# CFG_FLASH_Update.net
KiCad netlist of a schematic drawn in Altium Designer
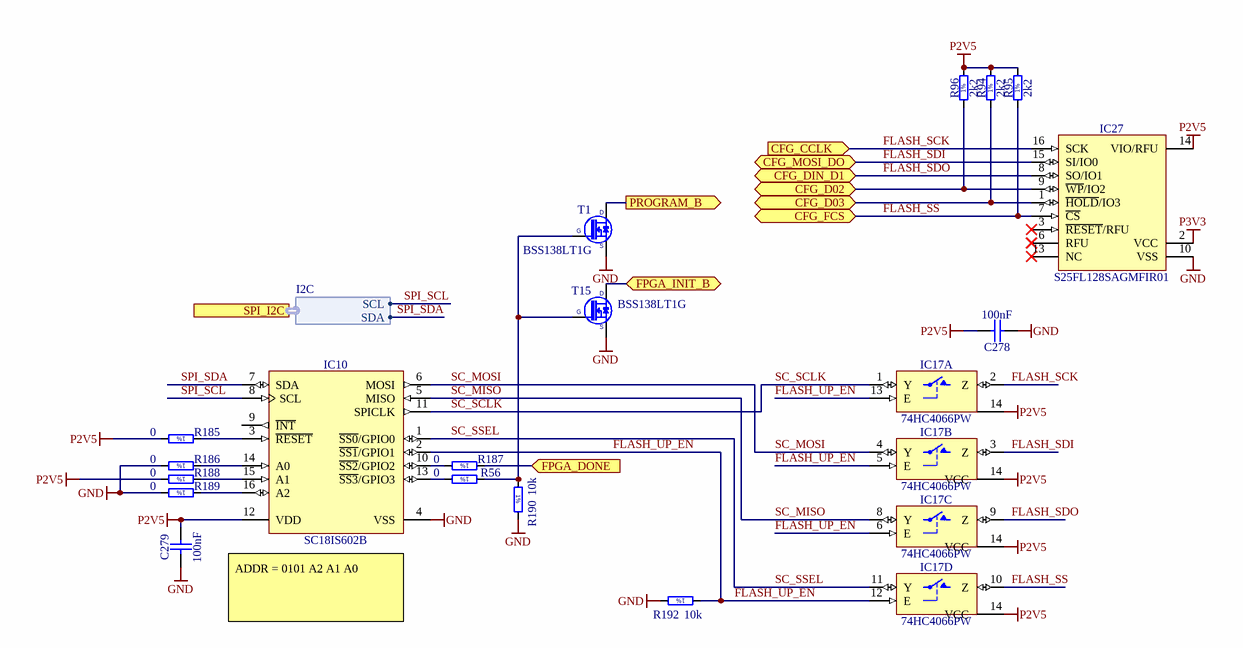
[diagram p0: CFG_FLASH_Update.SchDoc]

(export (version "E")
  (design (tool "Eeschema 10.0.6"))
  (components
    (comp (ref "C278")
      (value "100nF")
      (footprint "CAPC1005X55N")
      (description "Non-polarised capacitor")
      (fields
        (field (name "PART NUMBER") "CC0402_100NF_16V_10%_X5R")
        (field (name "VOLTAGE") "16V")
        (field (name "AUTHOR") "CERN DEM JLC")
      )
      (libsource (lib "Capacitors") (part "Capacitor - non polarized"))
    )
    (comp (ref "C279")
      (value "100nF")
      (footprint "CAPC1005X55N")
      (description "Non-polarised capacitor")
      (fields
        (field (name "PART NUMBER") "CC0402_100NF_16V_10%_X5R")
        (field (name "VOLTAGE") "16V")
        (field (name "AUTHOR") "CERN DEM JLC")
      )
      (libsource (lib "Capacitors") (part "Capacitor - non polarized"))
    )
    (comp (ref "IC10")
      (value "SC18IS602B")
      (footprint "SOP65P640X110-16N")
      (description "I2C-bus to SPI bridge")
      (fields (field (name "MANUFACTURER") "NXP SEMICONDUCTORS") (field (name "AUTHOR") "CERN DEM MR"))
      (libsource (lib "ICs And Semiconductors") (part "SC18IS602B"))
    )
    (comp (ref "IC17")
      (value "74HC4066PW")
      (footprint "SOP65P640X110-14N")
      (fields (field (name "MANUFACTURER") "NXP SEMICONDUCTORS") (field (name "AUTHOR") "CERN DEM JLC"))
      (libsource (lib "ICs And Semiconductors") (part "4066"))
    )
    (comp (ref "IC27")
      (value "S25FL128SAGMFIR01")
      (footprint "SOIC127P1030X265-16N")
      (fields (field (name "MANUFACTURER") "SPANSION") (field (name "AUTHOR") "CERN DEM JLC"))
      (libsource (lib "ICs And Semiconductors") (part "S25FL128SAGMFIR01"))
    )
    (comp (ref "R56")
      (value "0")
      (footprint "RESC1608X55N")
      (description "Resistor - 1%")
      (fields
        (field (name "PART NUMBER") "R0603_0R_JUMPER")
        (field (name "MANUFACTURER") "GENERIC")
        (field (name "AUTHOR") "CERN DEM JLC")
      )
      (libsource (lib "Resistors") (part "Resistor - 1%"))
    )
    (comp (ref "R94")
      (value "2k2")
      (footprint "RESC1005X40N")
      (description "Resistor - 1%")
      (fields
        (field (name "PART NUMBER") "R0402_2K2_1%_0.0625W_100PPM")
        (field (name "POWER") "0.0625W")
        (field (name "AUTHOR") "CERN DEM JLC")
      )
      (libsource (lib "Resistors") (part "Resistor - 1%"))
    )
    (comp (ref "R95")
      (value "2k2")
      (footprint "RESC1005X40N")
      (description "Resistor - 1%")
      (fields
        (field (name "PART NUMBER") "R0402_2K2_1%_0.0625W_100PPM")
        (field (name "POWER") "0.0625W")
        (field (name "AUTHOR") "CERN DEM JLC")
      )
      (libsource (lib "Resistors") (part "Resistor - 1%"))
    )
    (comp (ref "R96")
      (value "2k2")
      (footprint "RESC1005X40N")
      (description "Resistor - 1%")
      (fields
        (field (name "PART NUMBER") "R0402_2K2_1%_0.0625W_100PPM")
        (field (name "POWER") "0.0625W")
        (field (name "AUTHOR") "CERN DEM JLC")
      )
      (libsource (lib "Resistors") (part "Resistor - 1%"))
    )
    (comp (ref "R185")
      (value "0")
      (footprint "RESC1608X55N")
      (description "Resistor - 1%")
      (fields
        (field (name "PART NUMBER") "R0603_0R_JUMPER")
        (field (name "MANUFACTURER") "GENERIC")
        (field (name "AUTHOR") "CERN DEM JLC")
      )
      (libsource (lib "Resistors") (part "Resistor - 1%"))
    )
    (comp (ref "R186")
      (value "0")
      (footprint "RESC1608X55N")
      (description "Resistor - 1%")
      (fields
        (field (name "PART NUMBER") "R0603_0R_JUMPER")
        (field (name "MANUFACTURER") "GENERIC")
        (field (name "AUTHOR") "CERN DEM JLC")
      )
      (libsource (lib "Resistors") (part "Resistor - 1%"))
    )
    (comp (ref "R187")
      (value "0")
      (footprint "RESC1608X55N")
      (description "Resistor - 1%")
      (fields
        (field (name "PART NUMBER") "R0603_0R_JUMPER")
        (field (name "MANUFACTURER") "GENERIC")
        (field (name "AUTHOR") "CERN DEM JLC")
      )
      (libsource (lib "Resistors") (part "Resistor - 1%"))
    )
    (comp (ref "R188")
      (value "0")
      (footprint "RESC1608X55N")
      (description "Resistor - 1%")
      (fields
        (field (name "PART NUMBER") "R0603_0R_JUMPER")
        (field (name "MANUFACTURER") "GENERIC")
        (field (name "AUTHOR") "CERN DEM JLC")
      )
      (libsource (lib "Resistors") (part "Resistor - 1%"))
    )
    (comp (ref "R189")
      (value "0")
      (footprint "RESC1608X55N")
      (description "Resistor - 1%")
      (fields
        (field (name "PART NUMBER") "R0603_0R_JUMPER")
        (field (name "MANUFACTURER") "GENERIC")
        (field (name "AUTHOR") "CERN DEM JLC")
      )
      (libsource (lib "Resistors") (part "Resistor - 1%"))
    )
    (comp (ref "R190")
      (value "10k")
      (footprint "RESC1005X40N")
      (description "Resistor - 1%")
      (fields
        (field (name "PART NUMBER") "R0402_10K_1%_0.0625W_100PPM")
        (field (name "POWER") "0.0625W")
        (field (name "AUTHOR") "CERN DEM JLC")
      )
      (libsource (lib "Resistors") (part "Resistor - 1%"))
    )
    (comp (ref "R192")
      (value "10k")
      (footprint "RESC1005X40N")
      (description "Resistor - 1%")
      (fields
        (field (name "PART NUMBER") "R0402_10K_1%_0.0625W_100PPM")
        (field (name "POWER") "0.0625W")
        (field (name "AUTHOR") "CERN DEM JLC")
      )
      (libsource (lib "Resistors") (part "Resistor - 1%"))
    )
    (comp (ref "T1")
      (value "BSS138LT1G")
      (footprint "SOT95P240X110-3N")
      (description "N-CHANNEL MOSFET WITH DIODE")
      (fields (field (name "MANUFACTURER") "ON SEMICONDUCTOR") (field (name "AUTHOR") "CERN DEM JLC"))
      (libsource (lib "ICs And Semiconductors") (part "N-MOSFET-D 1G 2S 3D"))
    )
    (comp (ref "T15")
      (value "BSS138LT1G")
      (footprint "SOT95P240X110-3N")
      (description "N-CHANNEL MOSFET WITH DIODE")
      (fields (field (name "MANUFACTURER") "ON SEMICONDUCTOR") (field (name "AUTHOR") "CERN DEM JLC"))
      (libsource (lib "ICs And Semiconductors") (part "N-MOSFET-D 1G 2S 3D"))
    )
  )
  (nets
    (net (code "2") (name "/CFG_D02") (class "Default")
      (node (ref "IC27") (pin "9") (pinfunction "~{WP}/IO2_9") (pintype "bidirectional"))
      (node (ref "R96") (pin "1") (pinfunction "1_1") (pintype "passive"))
    )
    (net (code "3") (name "/CFG_D03") (class "Default")
      (node (ref "IC27") (pin "1") (pinfunction "~{HOLD}/IO3_1") (pintype "bidirectional"))
      (node (ref "R94") (pin "1") (pinfunction "1_1") (pintype "passive"))
    )
    (net (code "4") (name "/FLASH_SCK") (class "Default")
      (node (ref "IC17") (pin "2") (pinfunction "Z_2") (pintype "bidirectional"))
      (node (ref "IC27") (pin "16") (pinfunction "SCK_16") (pintype "input"))
    )
    (net (code "5") (name "/FLASH_SDI") (class "Default")
      (node (ref "IC17") (pin "3") (pinfunction "Z_3") (pintype "bidirectional"))
      (node (ref "IC27") (pin "15") (pinfunction "SI/IO0_15") (pintype "bidirectional"))
    )
    (net (code "6") (name "/FLASH_SDO") (class "Default")
      (node (ref "IC17") (pin "9") (pinfunction "Z_9") (pintype "bidirectional"))
      (node (ref "IC27") (pin "8") (pinfunction "SO/IO1_8") (pintype "bidirectional"))
    )
    (net (code "7") (name "/FLASH_SS") (class "Default")
      (node (ref "IC17") (pin "10") (pinfunction "Z_10") (pintype "bidirectional"))
      (node (ref "IC27") (pin "7") (pinfunction "~{CS}_7") (pintype "input"))
      (node (ref "R95") (pin "1") (pinfunction "1_1") (pintype "passive"))
    )
    (net (code "8") (name "/FLASH_UP_EN") (class "Default")
      (node (ref "IC10") (pin "2") (pinfunction "~{SS1}/GPIO1_2") (pintype "bidirectional"))
      (node (ref "IC17") (pin "12") (pinfunction "E_12") (pintype "input"))
      (node (ref "IC17") (pin "13") (pinfunction "E_13") (pintype "input"))
      (node (ref "IC17") (pin "5") (pinfunction "E_5") (pintype "input"))
      (node (ref "IC17") (pin "6") (pinfunction "E_6") (pintype "input"))
      (node (ref "R192") (pin "1") (pinfunction "1_1") (pintype "passive"))
    )
    (net (code "9") (name "/FPGA_DONE") (class "Default")
      (node (ref "R187") (pin "1") (pinfunction "1_1") (pintype "passive"))
    )
    (net (code "10") (name "/FPGA_INIT_B") (class "Default")
      (node (ref "T15") (pin "3") (pinfunction "D_3") (pintype "passive"))
    )
    (net (code "11") (name "/PROGRAM_B") (class "Default")
      (node (ref "T1") (pin "3") (pinfunction "D_3") (pintype "passive"))
    )
    (net (code "12") (name "/SC_MISO") (class "Default")
      (node (ref "IC10") (pin "5") (pinfunction "MISO_5") (pintype "input"))
      (node (ref "IC17") (pin "8") (pinfunction "Y_8") (pintype "bidirectional"))
    )
    (net (code "13") (name "/SC_MOSI") (class "Default")
      (node (ref "IC10") (pin "6") (pinfunction "MOSI_6") (pintype "output"))
      (node (ref "IC17") (pin "4") (pinfunction "Y_4") (pintype "bidirectional"))
    )
    (net (code "14") (name "/SC_SCLK") (class "Default")
      (node (ref "IC10") (pin "11") (pinfunction "SPICLK_11") (pintype "output"))
      (node (ref "IC17") (pin "1") (pinfunction "Y_1") (pintype "bidirectional"))
    )
    (net (code "15") (name "/SC_SSEL") (class "Default")
      (node (ref "IC10") (pin "1") (pinfunction "~{SS0}/GPIO0_1") (pintype "bidirectional"))
      (node (ref "IC17") (pin "11") (pinfunction "Y_11") (pintype "bidirectional"))
    )
    (net (code "16") (name "/SPI_SCL") (class "Default")
      (node (ref "IC10") (pin "8") (pinfunction "SCL_8") (pintype "input"))
    )
    (net (code "17") (name "/SPI_SDA") (class "Default")
      (node (ref "IC10") (pin "7") (pinfunction "SDA_7") (pintype "bidirectional"))
    )
    (net (code "19") (name "GND") (class "Default")
      (node (ref "C278") (pin "1") (pinfunction "1_1") (pintype "passive"))
      (node (ref "C279") (pin "1") (pinfunction "1_1") (pintype "passive"))
      (node (ref "IC10") (pin "4") (pinfunction "VSS_4") (pintype "power_in"))
      (node (ref "IC17") (pin "7") (pinfunction "GND_7") (pintype "power_in"))
      (node (ref "IC27") (pin "10") (pinfunction "VSS_10") (pintype "power_in"))
      (node (ref "R186") (pin "2") (pinfunction "2_2") (pintype "passive"))
      (node (ref "R189") (pin "2") (pinfunction "2_2") (pintype "passive"))
      (node (ref "R190") (pin "2") (pinfunction "2_2") (pintype "passive"))
      (node (ref "R192") (pin "2") (pinfunction "2_2") (pintype "passive"))
      (node (ref "T1") (pin "2") (pinfunction "S_2") (pintype "passive"))
      (node (ref "T15") (pin "2") (pinfunction "S_2") (pintype "passive"))
    )
    (net (code "20") (name "Net-(IC10-A0)") (class "Default")
      (node (ref "IC10") (pin "14") (pinfunction "A0_14") (pintype "input"))
      (node (ref "R186") (pin "1") (pinfunction "1_1") (pintype "passive"))
    )
    (net (code "21") (name "Net-(IC10-A1)") (class "Default")
      (node (ref "IC10") (pin "15") (pinfunction "A1_15") (pintype "input"))
      (node (ref "R188") (pin "1") (pinfunction "1_1") (pintype "passive"))
    )
    (net (code "22") (name "Net-(IC10-A2)") (class "Default")
      (node (ref "IC10") (pin "16") (pinfunction "A2_16") (pintype "bidirectional"))
      (node (ref "R189") (pin "1") (pinfunction "1_1") (pintype "passive"))
    )
    (net (code "23") (name "Net-(IC10-~{RESET})") (class "Default")
      (node (ref "IC10") (pin "3") (pinfunction "~{RESET}_3") (pintype "input"))
      (node (ref "R185") (pin "1") (pinfunction "1_1") (pintype "passive"))
    )
    (net (code "24") (name "Net-(IC10-~{SS2}{slash}GPIO2)") (class "Default")
      (node (ref "IC10") (pin "10") (pinfunction "~{SS2}/GPIO2_10") (pintype "bidirectional"))
      (node (ref "R187") (pin "2") (pinfunction "2_2") (pintype "passive"))
    )
    (net (code "25") (name "Net-(IC10-~{SS3}{slash}GPIO3)") (class "Default")
      (node (ref "IC10") (pin "13") (pinfunction "~{SS3}/GPIO3_13") (pintype "bidirectional"))
      (node (ref "R56") (pin "2") (pinfunction "2_2") (pintype "passive"))
    )
    (net (code "26") (name "Net-(T1-G)") (class "Default")
      (node (ref "R190") (pin "1") (pinfunction "1_1") (pintype "passive"))
      (node (ref "R56") (pin "1") (pinfunction "1_1") (pintype "passive"))
      (node (ref "T1") (pin "1") (pinfunction "G_1") (pintype "passive"))
      (node (ref "T15") (pin "1") (pinfunction "G_1") (pintype "passive"))
    )
    (net (code "27") (name "P2V5") (class "Default")
      (node (ref "C278") (pin "2") (pinfunction "2_2") (pintype "passive"))
      (node (ref "C279") (pin "2") (pinfunction "2_2") (pintype "passive"))
      (node (ref "IC10") (pin "12") (pinfunction "VDD_12") (pintype "power_in"))
      (node (ref "IC17") (pin "14") (pinfunction "VCC_14") (pintype "power_in"))
      (node (ref "IC27") (pin "14") (pinfunction "VIO/RFU_14") (pintype "power_in"))
      (node (ref "R185") (pin "2") (pinfunction "2_2") (pintype "passive"))
      (node (ref "R188") (pin "2") (pinfunction "2_2") (pintype "passive"))
      (node (ref "R94") (pin "2") (pinfunction "2_2") (pintype "passive"))
      (node (ref "R95") (pin "2") (pinfunction "2_2") (pintype "passive"))
      (node (ref "R96") (pin "2") (pinfunction "2_2") (pintype "passive"))
    )
    (net (code "28") (name "P3V3") (class "Default")
      (node (ref "IC27") (pin "2") (pinfunction "VCC_2") (pintype "power_in"))
    )
    (net (code "29") (name "unconnected-(IC10-~{INT}-Pad9)") (class "Default")
      (node (ref "IC10") (pin "9") (pinfunction "~{INT}_9") (pintype "output"))
    )
    (net (code "30") (name "unconnected-(IC27-NC-Pad13)") (class "Default")
      (node (ref "IC27") (pin "13") (pinfunction "NC_13") (pintype "passive+no_connect"))
    )
    (net (code "31") (name "unconnected-(IC27-RFU-Pad6)") (class "Default")
      (node (ref "IC27") (pin "6") (pinfunction "RFU_6") (pintype "passive+no_connect"))
    )
    (net (code "32") (name "unconnected-(IC27-~{RESET}{slash}RFU-Pad3)") (class "Default")
      (node (ref "IC27") (pin "3") (pinfunction "~{RESET}/RFU_3") (pintype "input+no_connect"))
    )
  )
)
